# Sheet1.net
KiCad netlist of a schematic drawn in Altium Designer
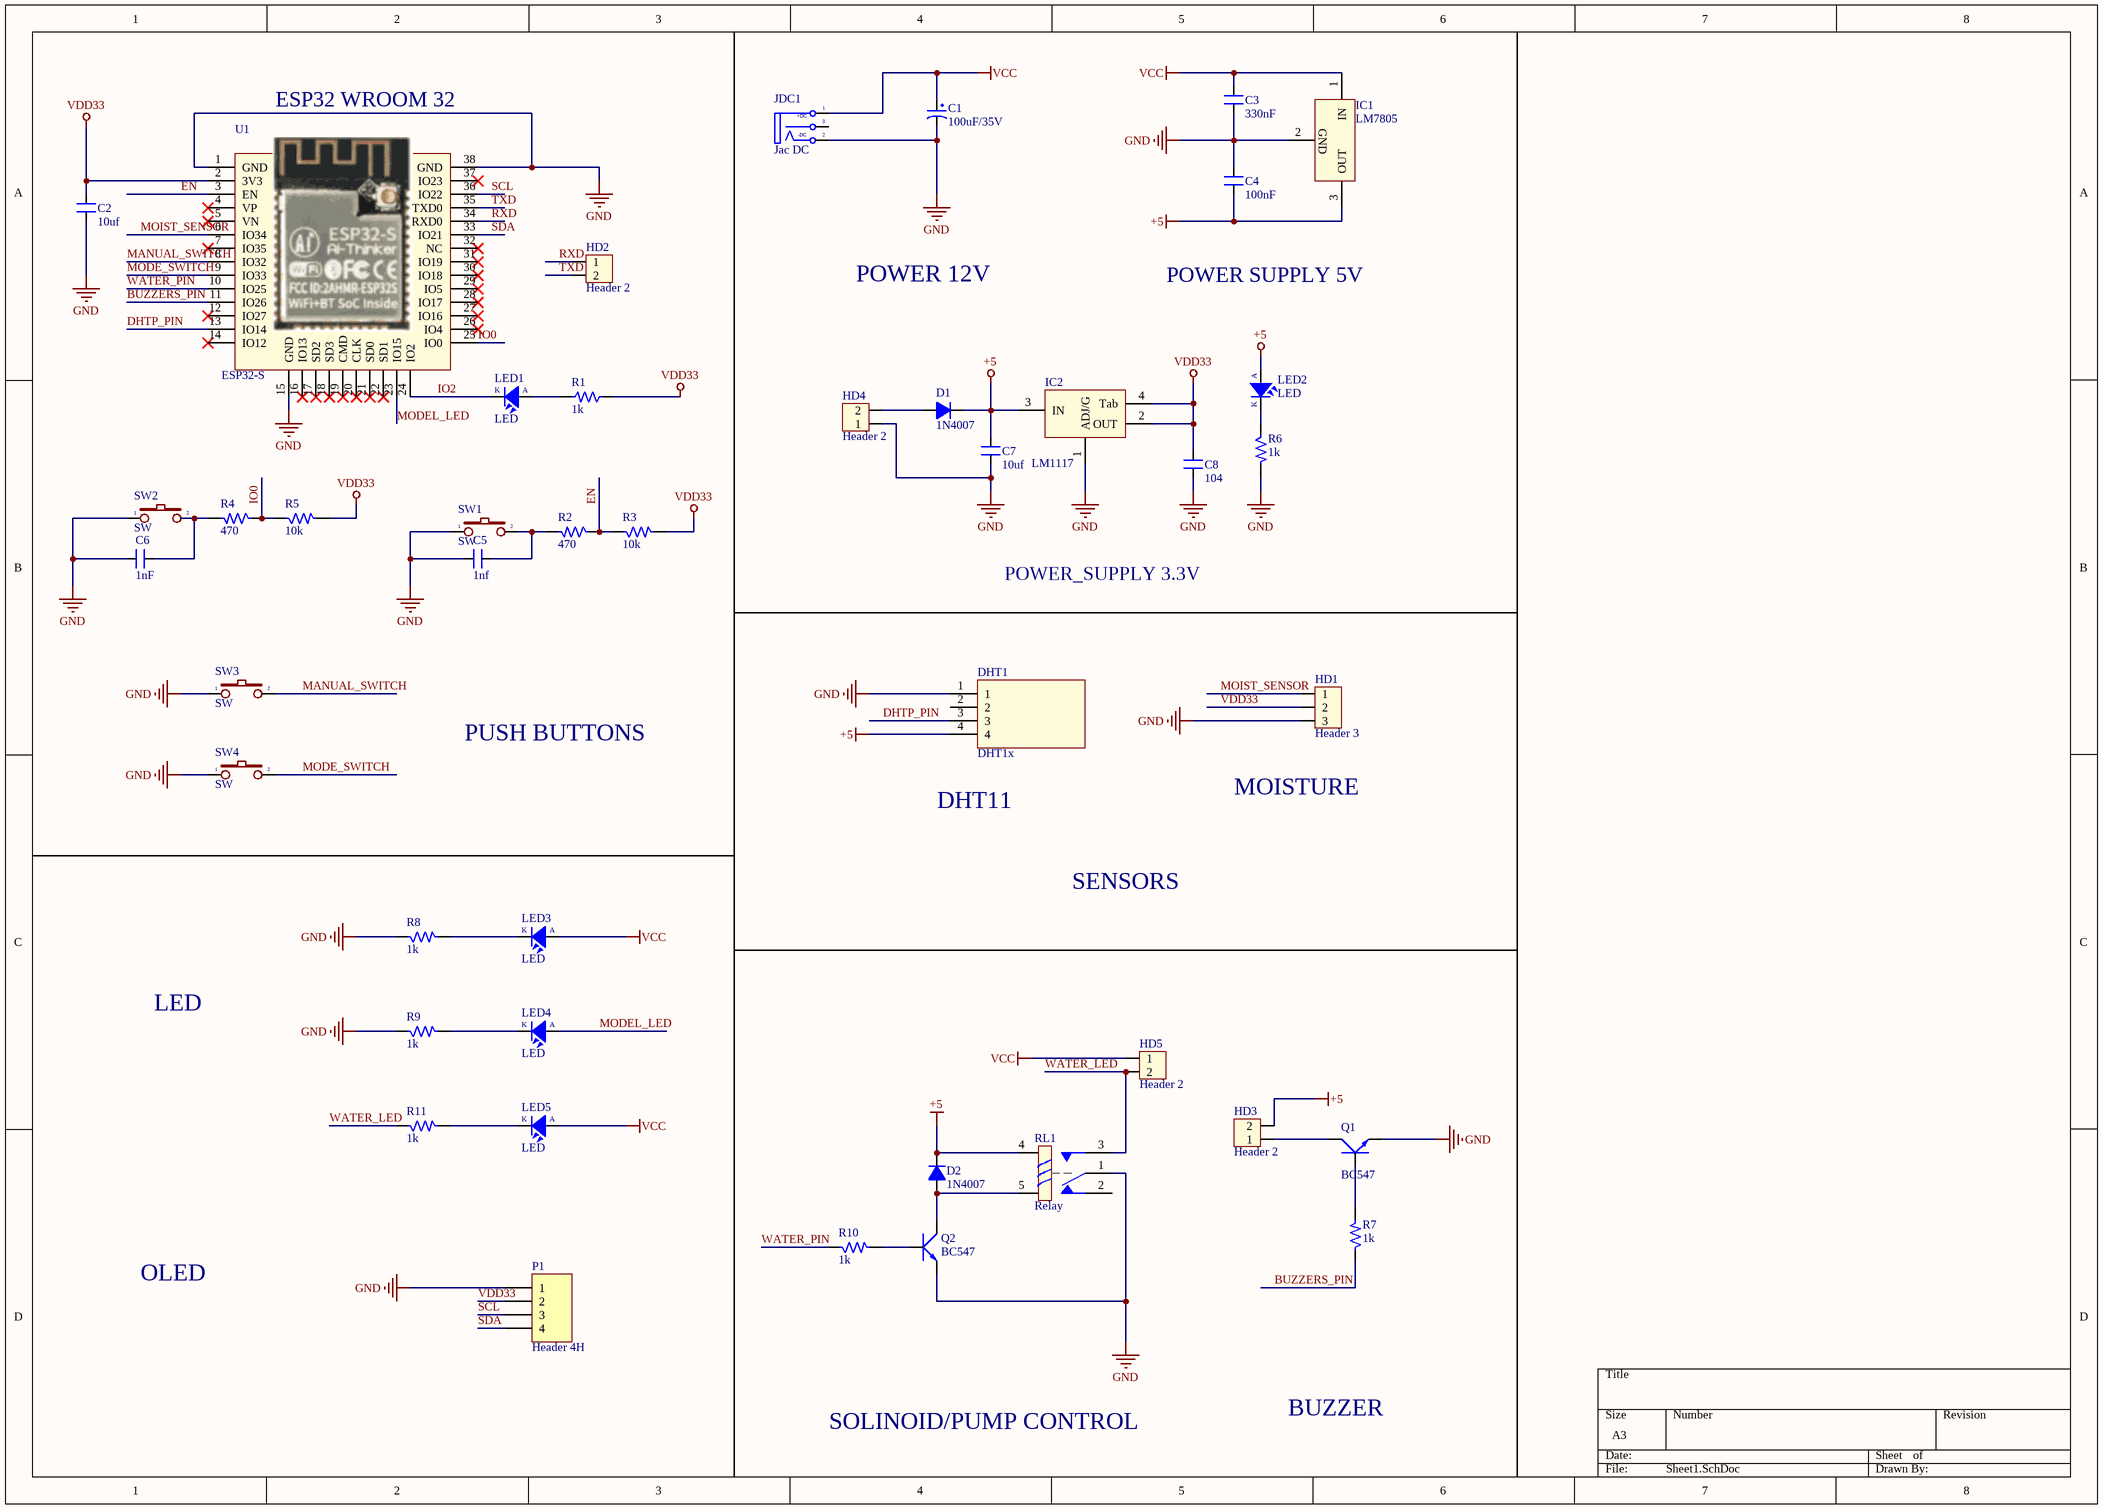
[diagram p0: Sheet1.SchDoc]

(export (version "E")
  (design (tool "Eeschema 10.0.6"))
  (components
    (comp (ref "C1")
      (value "100uF/35V")
      (footprint "CP1.5/3.4")
      (description "Cap 100uF/35V - 470uF/16V")
      (libsource (lib "PART_VDE") (part "CP3"))
    )
    (comp (ref "C2")
      (value "10uf")
      (footprint "CM-1206")
      (description "Cap SMD")
      (libsource (lib "PART_VDE") (part "CM"))
    )
    (comp (ref "C3")
      (value "330nF")
      (footprint "CM-0805")
      (description "Cap SMD")
      (libsource (lib "PART_VDE") (part "CM"))
    )
    (comp (ref "C4")
      (value "100nF")
      (footprint "CM-0805")
      (description "Cap SMD")
      (libsource (lib "PART_VDE") (part "CM"))
    )
    (comp (ref "C5")
      (value "1nf")
      (footprint "CM-0805")
      (description "Cap SMD")
      (libsource (lib "PART_VDE") (part "CM"))
    )
    (comp (ref "C6")
      (value "1nF")
      (footprint "CM-0805")
      (description "Cap SMD")
      (libsource (lib "PART_VDE") (part "CM"))
    )
    (comp (ref "C7")
      (value "10uf")
      (footprint "CM-0805")
      (description "Cap SMD")
      (libsource (lib "PART_VDE") (part "CM"))
    )
    (comp (ref "C8")
      (value "104")
      (footprint "CM-0805")
      (description "Cap SMD")
      (libsource (lib "PART_VDE") (part "CM"))
    )
    (comp (ref "D1")
      (value "1N4007")
      (footprint "D-0805 SOD323")
      (description "Diode 1A")
      (libsource (lib "PART_VDE") (part "D1A"))
    )
    (comp (ref "D2")
      (value "1N4007")
      (footprint "D-0805 SOD323")
      (description "Diode 1A")
      (libsource (lib "PART_VDE") (part "D1A"))
    )
    (comp (ref "DHT1")
      (value "DHT1x")
      (footprint "jp4")
      (description "Humidity and Temperature Sensor")
      (libsource (lib "PART_VDE") (part "DHT1x"))
    )
    (comp (ref "HD1")
      (value "Header 3")
      (footprint "HED3")
      (description "Header 3 (Green)")
      (libsource (lib "PART_VDE") (part "Hed3"))
    )
    (comp (ref "HD2")
      (value "Header 2")
      (footprint "HED2")
      (description "Header 2 (Green)")
      (libsource (lib "") (part "Hed2_1"))
    )
    (comp (ref "HD3")
      (value "Header 2")
      (footprint "HED2")
      (description "Header 2 (Green)")
      (libsource (lib "PART_VDE") (part "Hed2"))
    )
    (comp (ref "HD4")
      (value "Header 2")
      (footprint "HED2")
      (description "Header 2 (Green)")
      (libsource (lib "PART_VDE") (part "Hed2"))
    )
    (comp (ref "HD5")
      (value "Header 2")
      (footprint "HED2")
      (description "Header 2 (Green)")
      (libsource (lib "") (part "Hed2_1"))
    )
    (comp (ref "IC1")
      (value "LM7805")
      (footprint "QTO-220H1")
      (description "On ap +, from + 5 to + 24VDC")
      (libsource (lib "PART_VDE") (part "LM78xx"))
    )
    (comp (ref "IC2")
      (value "LM1117")
      (footprint "SOT223-4N")
      (description "3v3")
      (libsource (lib "PART_VDE") (part "LM1117"))
    )
    (comp (ref "JDC1")
      (value "Jac DC")
      (footprint "DC-IN")
      (description "Jac DC input")
      (libsource (lib "PART_VDE") (part "DCIN"))
    )
    (comp (ref "LED1")
      (value "LED")
      (footprint "LED-0805")
      (description "LED Single colour Green and Red")
      (libsource (lib "PART_VDE") (part "LED"))
    )
    (comp (ref "LED2")
      (value "LED")
      (footprint "LED-0805")
      (description "LED Single colour Green and Red")
      (libsource (lib "PART_VDE") (part "LED"))
    )
    (comp (ref "LED3")
      (value "LED")
      (footprint "LED-0805")
      (description "LED Single colour Green and Red")
      (libsource (lib "PART_VDE") (part "LED"))
    )
    (comp (ref "LED4")
      (value "LED")
      (footprint "LED-0805")
      (description "LED Single colour Green and Red")
      (libsource (lib "PART_VDE") (part "LED"))
    )
    (comp (ref "LED5")
      (value "LED")
      (footprint "LED-0805")
      (description "LED Single colour Green and Red")
      (libsource (lib "PART_VDE") (part "LED"))
    )
    (comp (ref "P1")
      (value "Header 4H")
      (footprint "HDR1X4H")
      (description "Header, 4-Pin, Right Angle")
      (fields (field (name "PUBLISHER") "Altium Limited"))
      (libsource (lib "Miscellaneous Connectors") (part "Header 4H"))
    )
    (comp (ref "Q1")
      (value "BC547")
      (footprint "QTO-92")
      (description "P 600mW, CBE")
      (libsource (lib "PART_VDE") (part "BC547"))
    )
    (comp (ref "Q2")
      (value "BC547")
      (footprint "QTO-92")
      (description "P 600mW, CBE")
      (libsource (lib "PART_VDE") (part "BC547"))
    )
    (comp (ref "R1")
      (value "1k")
      (footprint "RM-1206")
      (description "Resistor 1/4W")
      (libsource (lib "PART_VDE") (part "R"))
    )
    (comp (ref "R2")
      (value "470")
      (footprint "RM-0805")
      (description "Resistor 1/4W")
      (libsource (lib "PART_VDE") (part "R"))
    )
    (comp (ref "R3")
      (value "10k")
      (footprint "RM-1206")
      (description "Resistor 1/4W")
      (libsource (lib "PART_VDE") (part "R"))
    )
    (comp (ref "R4")
      (value "470")
      (footprint "RM-0805")
      (description "Resistor 1/4W")
      (libsource (lib "PART_VDE") (part "R"))
    )
    (comp (ref "R5")
      (value "10k")
      (footprint "RM-1206")
      (description "Resistor 1/4W")
      (libsource (lib "PART_VDE") (part "R"))
    )
    (comp (ref "R6")
      (value "1k")
      (footprint "RM-0805")
      (description "Resistor 1/4W")
      (libsource (lib "PART_VDE") (part "R"))
    )
    (comp (ref "R7")
      (value "1k")
      (footprint "RM-1206")
      (description "Resistor 1/4W")
      (libsource (lib "PART_VDE") (part "R"))
    )
    (comp (ref "R8")
      (value "1k")
      (footprint "RM-1206")
      (description "Resistor 1/4W")
      (libsource (lib "PART_VDE") (part "R"))
    )
    (comp (ref "R9")
      (value "1k")
      (footprint "RM-1206")
      (description "Resistor 1/4W")
      (libsource (lib "PART_VDE") (part "R"))
    )
    (comp (ref "R10")
      (value "1k")
      (footprint "RM-1206")
      (description "Resistor 1/4W")
      (libsource (lib "PART_VDE") (part "R"))
    )
    (comp (ref "R11")
      (value "1k")
      (footprint "RM-1206")
      (description "Resistor 1/4W")
      (libsource (lib "PART_VDE") (part "R"))
    )
    (comp (ref "RL1")
      (value "Relay")
      (footprint "Relay HK23F")
      (description "Relay SPDT 5 Pin")
      (libsource (lib "PART_VDE") (part "Relay 1"))
    )
    (comp (ref "SW1")
      (value "SW")
      (footprint "SW-SMD3*6")
      (description "Switch button 2 pin")
      (libsource (lib "PART_VDE") (part "SW2"))
    )
    (comp (ref "SW2")
      (value "SW")
      (footprint "SW-SMD3*6")
      (description "Switch button 2 pin")
      (libsource (lib "PART_VDE") (part "SW2"))
    )
    (comp (ref "SW3")
      (value "SW")
      (footprint "SW-SMD3*6")
      (description "Switch button 2 pin")
      (libsource (lib "PART_VDE") (part "SW2"))
    )
    (comp (ref "SW4")
      (value "SW")
      (footprint "SW-SMD3*6")
      (description "Switch button 2 pin")
      (libsource (lib "PART_VDE") (part "SW2"))
    )
    (comp (ref "U1") (value "ESP32-S") (footprint "ESP-32WR") (libsource (lib "PART_VDE") (part "ESP32-S")))
  )
  (nets
    (net (code "1") (name "+5") (class "Default")
      (node (ref "C4") (pin "1") (pinfunction "1_1") (pintype "passive"))
      (node (ref "C7") (pin "2") (pinfunction "2_2") (pintype "passive"))
      (node (ref "D1") (pin "2") (pinfunction "K_2") (pintype "passive"))
      (node (ref "D2") (pin "2") (pinfunction "K_2") (pintype "passive"))
      (node (ref "DHT1") (pin "4") (pinfunction "4_4") (pintype "passive"))
      (node (ref "HD3") (pin "2") (pinfunction "2_2") (pintype "passive"))
      (node (ref "IC1") (pin "3") (pinfunction "OUT_3") (pintype "passive"))
      (node (ref "IC2") (pin "3") (pinfunction "IN_3") (pintype "passive"))
      (node (ref "LED2") (pin "1") (pinfunction "A_1") (pintype "passive"))
      (node (ref "RL1") (pin "4") (pinfunction "4_4") (pintype "passive"))
    )
    (net (code "2") (name "/BUZZERS_PIN") (class "Default")
      (node (ref "R7") (pin "1") (pinfunction "1_1") (pintype "passive"))
      (node (ref "U1") (pin "11") (pinfunction "IO26_11") (pintype "passive"))
    )
    (net (code "3") (name "/DHTP_PIN") (class "Default")
      (node (ref "DHT1") (pin "3") (pinfunction "3_3") (pintype "passive"))
      (node (ref "U1") (pin "13") (pinfunction "IO14_13") (pintype "passive"))
    )
    (net (code "4") (name "/EN") (class "Default")
      (node (ref "R2") (pin "1") (pinfunction "1_1") (pintype "passive"))
      (node (ref "R3") (pin "1") (pinfunction "1_1") (pintype "passive"))
      (node (ref "U1") (pin "3") (pinfunction "EN_3") (pintype "passive"))
    )
    (net (code "5") (name "/IO0") (class "Default")
      (node (ref "R4") (pin "1") (pinfunction "1_1") (pintype "passive"))
      (node (ref "R5") (pin "1") (pinfunction "1_1") (pintype "passive"))
      (node (ref "U1") (pin "25") (pinfunction "IO0_25") (pintype "passive"))
    )
    (net (code "6") (name "/IO2") (class "Default")
      (node (ref "LED1") (pin "2") (pinfunction "K_2") (pintype "passive"))
      (node (ref "U1") (pin "24") (pinfunction "IO2_24") (pintype "passive"))
    )
    (net (code "7") (name "/MANUAL_SWITCH") (class "Default")
      (node (ref "SW3") (pin "2") (pinfunction "2_2") (pintype "passive"))
      (node (ref "U1") (pin "8") (pinfunction "IO32_8") (pintype "passive"))
    )
    (net (code "8") (name "/MODEL_LED") (class "Default")
      (node (ref "LED4") (pin "1") (pinfunction "A_1") (pintype "passive"))
      (node (ref "U1") (pin "23") (pinfunction "IO15_23") (pintype "passive"))
    )
    (net (code "9") (name "/MODE_SWITCH") (class "Default")
      (node (ref "SW4") (pin "2") (pinfunction "2_2") (pintype "passive"))
      (node (ref "U1") (pin "9") (pinfunction "IO33_9") (pintype "passive"))
    )
    (net (code "10") (name "/MOIST_SENSOR") (class "Default")
      (node (ref "HD1") (pin "1") (pinfunction "1_1") (pintype "passive"))
      (node (ref "U1") (pin "6") (pinfunction "IO34_6") (pintype "passive"))
    )
    (net (code "11") (name "/RXD") (class "Default")
      (node (ref "HD2") (pin "1") (pinfunction "1_1") (pintype "passive"))
      (node (ref "U1") (pin "34") (pinfunction "RXD0_34") (pintype "passive"))
    )
    (net (code "12") (name "/SCL") (class "Default")
      (node (ref "P1") (pin "3") (pinfunction "3_3") (pintype "passive"))
      (node (ref "U1") (pin "36") (pinfunction "IO22_36") (pintype "passive"))
    )
    (net (code "13") (name "/SDA") (class "Default")
      (node (ref "P1") (pin "4") (pinfunction "4_4") (pintype "passive"))
      (node (ref "U1") (pin "33") (pinfunction "IO21_33") (pintype "passive"))
    )
    (net (code "14") (name "/TXD") (class "Default")
      (node (ref "HD2") (pin "2") (pinfunction "2_2") (pintype "passive"))
      (node (ref "U1") (pin "35") (pinfunction "TXD0_35") (pintype "passive"))
    )
    (net (code "15") (name "/WATER_LED") (class "Default")
      (node (ref "HD5") (pin "2") (pinfunction "2_2") (pintype "passive"))
      (node (ref "R11") (pin "1") (pinfunction "1_1") (pintype "passive"))
      (node (ref "RL1") (pin "3") (pinfunction "3_3") (pintype "passive"))
    )
    (net (code "16") (name "/WATER_PIN") (class "Default")
      (node (ref "R10") (pin "1") (pinfunction "1_1") (pintype "passive"))
      (node (ref "U1") (pin "10") (pinfunction "IO25_10") (pintype "passive"))
    )
    (net (code "17") (name "GND") (class "Default")
      (node (ref "C1") (pin "2") (pinfunction "2_2") (pintype "passive"))
      (node (ref "C2") (pin "1") (pinfunction "1_1") (pintype "passive"))
      (node (ref "C3") (pin "1") (pinfunction "1_1") (pintype "passive"))
      (node (ref "C4") (pin "2") (pinfunction "2_2") (pintype "passive"))
      (node (ref "C5") (pin "2") (pinfunction "2_2") (pintype "passive"))
      (node (ref "C6") (pin "2") (pinfunction "2_2") (pintype "passive"))
      (node (ref "C7") (pin "1") (pinfunction "1_1") (pintype "passive"))
      (node (ref "C8") (pin "1") (pinfunction "1_1") (pintype "passive"))
      (node (ref "DHT1") (pin "1") (pinfunction "1_1") (pintype "passive"))
      (node (ref "HD1") (pin "3") (pinfunction "3_3") (pintype "passive"))
      (node (ref "HD4") (pin "1") (pinfunction "1_1") (pintype "passive"))
      (node (ref "IC1") (pin "2") (pinfunction "GND_2") (pintype "passive"))
      (node (ref "IC2") (pin "1") (pinfunction "ADJ/G_1") (pintype "passive"))
      (node (ref "JDC1") (pin "2") (pinfunction "TN_2") (pintype "passive"))
      (node (ref "P1") (pin "1") (pinfunction "1_1") (pintype "passive"))
      (node (ref "Q1") (pin "3") (pinfunction "E_3") (pintype "passive"))
      (node (ref "Q2") (pin "3") (pinfunction "E_3") (pintype "passive"))
      (node (ref "R6") (pin "2") (pinfunction "2_2") (pintype "passive"))
      (node (ref "R8") (pin "1") (pinfunction "1_1") (pintype "passive"))
      (node (ref "R9") (pin "1") (pinfunction "1_1") (pintype "passive"))
      (node (ref "RL1") (pin "1") (pinfunction "1_1") (pintype "passive"))
      (node (ref "SW1") (pin "1") (pinfunction "1_1") (pintype "passive"))
      (node (ref "SW2") (pin "1") (pinfunction "1_1") (pintype "passive"))
      (node (ref "SW3") (pin "1") (pinfunction "1_1") (pintype "passive"))
      (node (ref "SW4") (pin "1") (pinfunction "1_1") (pintype "passive"))
      (node (ref "U1") (pin "1") (pinfunction "GND_1") (pintype "passive"))
      (node (ref "U1") (pin "15") (pinfunction "GND_15") (pintype "passive"))
      (node (ref "U1") (pin "38") (pinfunction "GND_38") (pintype "passive"))
    )
    (net (code "18") (name "Net-(C5-Pad1)") (class "Default")
      (node (ref "C5") (pin "1") (pinfunction "1_1") (pintype "passive"))
      (node (ref "R2") (pin "2") (pinfunction "2_2") (pintype "passive"))
      (node (ref "SW1") (pin "2") (pinfunction "2_2") (pintype "passive"))
    )
    (net (code "19") (name "Net-(C6-Pad1)") (class "Default")
      (node (ref "C6") (pin "1") (pinfunction "1_1") (pintype "passive"))
      (node (ref "R4") (pin "2") (pinfunction "2_2") (pintype "passive"))
      (node (ref "SW2") (pin "2") (pinfunction "2_2") (pintype "passive"))
    )
    (net (code "20") (name "Net-(D1-A)") (class "Default")
      (node (ref "D1") (pin "1") (pinfunction "A_1") (pintype "passive"))
      (node (ref "HD4") (pin "2") (pinfunction "2_2") (pintype "passive"))
    )
    (net (code "21") (name "Net-(D2-A)") (class "Default")
      (node (ref "D2") (pin "1") (pinfunction "A_1") (pintype "passive"))
      (node (ref "Q2") (pin "1") (pinfunction "C_1") (pintype "passive"))
      (node (ref "RL1") (pin "5") (pinfunction "5_5") (pintype "passive"))
    )
    (net (code "22") (name "Net-(LED1-A)") (class "Default")
      (node (ref "LED1") (pin "1") (pinfunction "A_1") (pintype "passive"))
      (node (ref "R1") (pin "2") (pinfunction "2_2") (pintype "passive"))
    )
    (net (code "23") (name "Net-(LED2-K)") (class "Default")
      (node (ref "LED2") (pin "2") (pinfunction "K_2") (pintype "passive"))
      (node (ref "R6") (pin "1") (pinfunction "1_1") (pintype "passive"))
    )
    (net (code "24") (name "Net-(LED3-K)") (class "Default")
      (node (ref "LED3") (pin "2") (pinfunction "K_2") (pintype "passive"))
      (node (ref "R8") (pin "2") (pinfunction "2_2") (pintype "passive"))
    )
    (net (code "25") (name "Net-(LED4-K)") (class "Default")
      (node (ref "LED4") (pin "2") (pinfunction "K_2") (pintype "passive"))
      (node (ref "R9") (pin "2") (pinfunction "2_2") (pintype "passive"))
    )
    (net (code "26") (name "Net-(LED5-K)") (class "Default")
      (node (ref "LED5") (pin "2") (pinfunction "K_2") (pintype "passive"))
      (node (ref "R11") (pin "2") (pinfunction "2_2") (pintype "passive"))
    )
    (net (code "27") (name "Net-(Q1-B)") (class "Default")
      (node (ref "Q1") (pin "2") (pinfunction "B_2") (pintype "passive"))
      (node (ref "R7") (pin "2") (pinfunction "2_2") (pintype "passive"))
    )
    (net (code "28") (name "Net-(Q1-C)") (class "Default")
      (node (ref "HD3") (pin "1") (pinfunction "1_1") (pintype "passive"))
      (node (ref "Q1") (pin "1") (pinfunction "C_1") (pintype "passive"))
    )
    (net (code "29") (name "Net-(Q2-B)") (class "Default")
      (node (ref "Q2") (pin "2") (pinfunction "B_2") (pintype "passive"))
      (node (ref "R10") (pin "2") (pinfunction "2_2") (pintype "passive"))
    )
    (net (code "30") (name "VCC") (class "Default")
      (node (ref "C1") (pin "1") (pinfunction "1_1") (pintype "passive"))
      (node (ref "C3") (pin "2") (pinfunction "2_2") (pintype "passive"))
      (node (ref "HD5") (pin "1") (pinfunction "1_1") (pintype "passive"))
      (node (ref "IC1") (pin "1") (pinfunction "IN_1") (pintype "passive"))
      (node (ref "JDC1") (pin "1") (pinfunction "+DC_1") (pintype "passive"))
      (node (ref "LED3") (pin "1") (pinfunction "A_1") (pintype "passive"))
      (node (ref "LED5") (pin "1") (pinfunction "A_1") (pintype "passive"))
    )
    (net (code "31") (name "VDD33") (class "Default")
      (node (ref "C2") (pin "2") (pinfunction "2_2") (pintype "passive"))
      (node (ref "C8") (pin "2") (pinfunction "2_2") (pintype "passive"))
      (node (ref "HD1") (pin "2") (pinfunction "2_2") (pintype "passive"))
      (node (ref "IC2") (pin "2") (pinfunction "OUT_2") (pintype "passive"))
      (node (ref "IC2") (pin "4") (pinfunction "Tab_4") (pintype "passive"))
      (node (ref "P1") (pin "2") (pinfunction "2_2") (pintype "passive"))
      (node (ref "R1") (pin "1") (pinfunction "1_1") (pintype "passive"))
      (node (ref "R3") (pin "2") (pinfunction "2_2") (pintype "passive"))
      (node (ref "R5") (pin "2") (pinfunction "2_2") (pintype "passive"))
      (node (ref "U1") (pin "2") (pinfunction "3V3_2") (pintype "passive"))
    )
    (net (code "32") (name "unconnected-(DHT1-Pad2)") (class "Default")
      (node (ref "DHT1") (pin "2") (pinfunction "2_2") (pintype "passive"))
    )
    (net (code "33") (name "unconnected-(JDC1-S-Pad3)") (class "Default")
      (node (ref "JDC1") (pin "3") (pinfunction "S_3") (pintype "power_in"))
    )
    (net (code "34") (name "unconnected-(RL1-Pad2)") (class "Default")
      (node (ref "RL1") (pin "2") (pinfunction "2_2") (pintype "passive"))
    )
    (net (code "35") (name "unconnected-(U1-CLK-Pad20)") (class "Default")
      (node (ref "U1") (pin "20") (pinfunction "CLK_20") (pintype "passive+no_connect"))
    )
    (net (code "36") (name "unconnected-(U1-CMD-Pad19)") (class "Default")
      (node (ref "U1") (pin "19") (pinfunction "CMD_19") (pintype "passive+no_connect"))
    )
    (net (code "37") (name "unconnected-(U1-IO4-Pad26)") (class "Default")
      (node (ref "U1") (pin "26") (pinfunction "IO4_26") (pintype "passive+no_connect"))
    )
    (net (code "38") (name "unconnected-(U1-IO5-Pad29)") (class "Default")
      (node (ref "U1") (pin "29") (pinfunction "IO5_29") (pintype "passive+no_connect"))
    )
    (net (code "39") (name "unconnected-(U1-IO12-Pad14)") (class "Default")
      (node (ref "U1") (pin "14") (pinfunction "IO12_14") (pintype "passive+no_connect"))
    )
    (net (code "40") (name "unconnected-(U1-IO13-Pad16)") (class "Default")
      (node (ref "U1") (pin "16") (pinfunction "IO13_16") (pintype "passive+no_connect"))
    )
    (net (code "41") (name "unconnected-(U1-IO16-Pad27)") (class "Default")
      (node (ref "U1") (pin "27") (pinfunction "IO16_27") (pintype "passive+no_connect"))
    )
    (net (code "42") (name "unconnected-(U1-IO17-Pad28)") (class "Default")
      (node (ref "U1") (pin "28") (pinfunction "IO17_28") (pintype "passive+no_connect"))
    )
    (net (code "43") (name "unconnected-(U1-IO18-Pad30)") (class "Default")
      (node (ref "U1") (pin "30") (pinfunction "IO18_30") (pintype "passive+no_connect"))
    )
    (net (code "44") (name "unconnected-(U1-IO19-Pad31)") (class "Default")
      (node (ref "U1") (pin "31") (pinfunction "IO19_31") (pintype "passive+no_connect"))
    )
    (net (code "45") (name "unconnected-(U1-IO23-Pad37)") (class "Default")
      (node (ref "U1") (pin "37") (pinfunction "IO23_37") (pintype "passive+no_connect"))
    )
    (net (code "46") (name "unconnected-(U1-IO27-Pad12)") (class "Default")
      (node (ref "U1") (pin "12") (pinfunction "IO27_12") (pintype "passive+no_connect"))
    )
    (net (code "47") (name "unconnected-(U1-IO35-Pad7)") (class "Default")
      (node (ref "U1") (pin "7") (pinfunction "IO35_7") (pintype "passive+no_connect"))
    )
    (net (code "48") (name "unconnected-(U1-NC-Pad32)") (class "Default")
      (node (ref "U1") (pin "32") (pinfunction "NC_32") (pintype "passive+no_connect"))
    )
    (net (code "49") (name "unconnected-(U1-SD0-Pad21)") (class "Default")
      (node (ref "U1") (pin "21") (pinfunction "SD0_21") (pintype "passive+no_connect"))
    )
    (net (code "50") (name "unconnected-(U1-SD1-Pad22)") (class "Default")
      (node (ref "U1") (pin "22") (pinfunction "SD1_22") (pintype "passive+no_connect"))
    )
    (net (code "51") (name "unconnected-(U1-SD2-Pad17)") (class "Default")
      (node (ref "U1") (pin "17") (pinfunction "SD2_17") (pintype "passive+no_connect"))
    )
    (net (code "52") (name "unconnected-(U1-SD3-Pad18)") (class "Default")
      (node (ref "U1") (pin "18") (pinfunction "SD3_18") (pintype "passive+no_connect"))
    )
    (net (code "53") (name "unconnected-(U1-VN-Pad5)") (class "Default")
      (node (ref "U1") (pin "5") (pinfunction "VN_5") (pintype "passive+no_connect"))
    )
    (net (code "54") (name "unconnected-(U1-VP-Pad4)") (class "Default")
      (node (ref "U1") (pin "4") (pinfunction "VP_4") (pintype "passive+no_connect"))
    )
  )
)
